# untitled.net
KiCad netlist of a schematic drawn in EAGLE
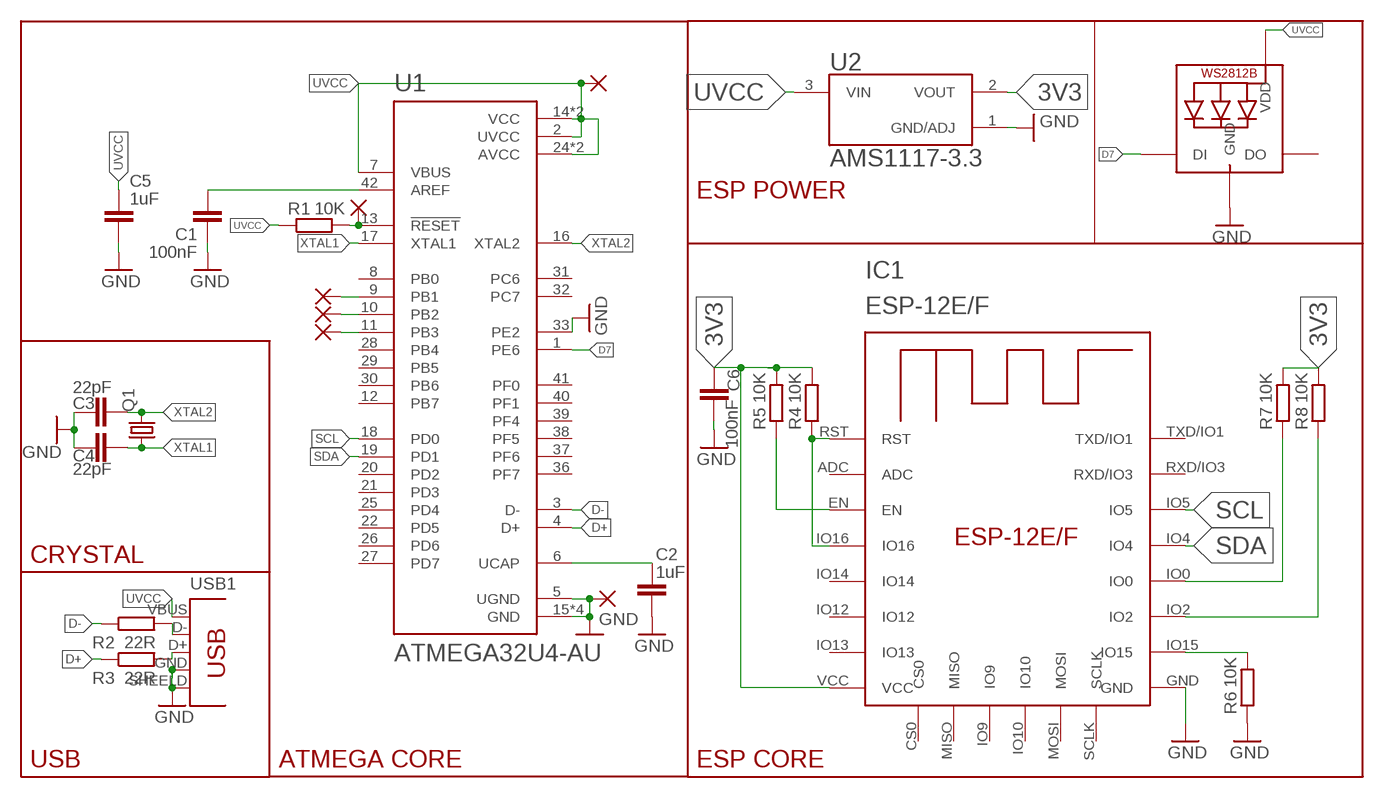
[diagram p0: schematic, sheet 1]

(export (version "E")
  (design (tool "Eeschema 10.0.6"))
  (components
    (comp (ref "C1")
      (value "100nF")
      (footprint "eagle-import:C0805")
      (libsource (lib "eagle-import") (part "C-EUC0805"))
    )
    (comp (ref "C2")
      (value "1uF")
      (footprint "eagle-import:C0805")
      (libsource (lib "eagle-import") (part "C-EUC0805"))
    )
    (comp (ref "C3")
      (value "22pF")
      (footprint "eagle-import:C0805")
      (libsource (lib "eagle-import") (part "C-EUC0805"))
    )
    (comp (ref "C4")
      (value "22pF")
      (footprint "eagle-import:C0805")
      (libsource (lib "eagle-import") (part "C-EUC0805"))
    )
    (comp (ref "C5")
      (value "1uF")
      (footprint "eagle-import:C0805")
      (libsource (lib "eagle-import") (part "C-EUC0805"))
    )
    (comp (ref "C6")
      (value "100nF")
      (footprint "eagle-import:C0805")
      (libsource (lib "eagle-import") (part "C-EUC0805"))
    )
    (comp (ref "IC1")
      (value "ESP-12E/F")
      (footprint "eagle-import:ESP-12E")
      (libsource (lib "eagle-import") (part "ESP-12E/F"))
    )
    (comp (ref "LED1")
      (value "WS2812B5050")
      (footprint "eagle-import:WS2812B")
      (fields (field (name "MF") "Worldsemi") (field (name "MP") "WS2812B"))
      (libsource (lib "eagle-import") (part "WS2812B5050"))
    )
    (comp (ref "PAD1")
      (value "1,6/0,8")
      (footprint "eagle-import:1,6_0,8")
      (libsource (lib "eagle-import") (part "1,6/0,8"))
    )
    (comp (ref "PAD2")
      (value "1,6/0,8")
      (footprint "eagle-import:1,6_0,8")
      (libsource (lib "eagle-import") (part "1,6/0,8"))
    )
    (comp (ref "PAD3")
      (value "1,6/0,8")
      (footprint "eagle-import:1,6_0,8")
      (libsource (lib "eagle-import") (part "1,6/0,8"))
    )
    (comp (ref "PAD4")
      (value "1,6/0,8")
      (footprint "eagle-import:1,6_0,8")
      (libsource (lib "eagle-import") (part "1,6/0,8"))
    )
    (comp (ref "PAD5")
      (value "1,6/0,8")
      (footprint "eagle-import:1,6_0,8")
      (libsource (lib "eagle-import") (part "1,6/0,8"))
    )
    (comp (ref "PAD6")
      (value "1,6/0,8")
      (footprint "eagle-import:1,6_0,8")
      (libsource (lib "eagle-import") (part "1,6/0,8"))
    )
    (comp (ref "Q1")
      (value "CRYSTALCTS406")
      (footprint "eagle-import:CTS406")
      (libsource (lib "eagle-import") (part "CRYSTALCTS406"))
    )
    (comp (ref "R1")
      (value "10K")
      (footprint "eagle-import:R0805")
      (libsource (lib "eagle-import") (part "R-EU_R0805"))
    )
    (comp (ref "R2")
      (value "22R")
      (footprint "eagle-import:R0805")
      (libsource (lib "eagle-import") (part "R-EU_R0805"))
    )
    (comp (ref "R3")
      (value "22R")
      (footprint "eagle-import:R0805")
      (libsource (lib "eagle-import") (part "R-EU_R0805"))
    )
    (comp (ref "R4")
      (value "10K")
      (footprint "eagle-import:R0805")
      (libsource (lib "eagle-import") (part "R-EU_R0805"))
    )
    (comp (ref "R5")
      (value "10K")
      (footprint "eagle-import:R0805")
      (libsource (lib "eagle-import") (part "R-EU_R0805"))
    )
    (comp (ref "R6")
      (value "10K")
      (footprint "eagle-import:R0805")
      (libsource (lib "eagle-import") (part "R-EU_R0805"))
    )
    (comp (ref "R7")
      (value "10K")
      (footprint "eagle-import:R0805")
      (libsource (lib "eagle-import") (part "R-EU_R0805"))
    )
    (comp (ref "R8")
      (value "10K")
      (footprint "eagle-import:R0805")
      (libsource (lib "eagle-import") (part "R-EU_R0805"))
    )
    (comp (ref "U1")
      (value "ATMEGA32U4-AU")
      (footprint "eagle-import:QFP80P1200X1200X120-44N")
      (fields (field (name "MF") "Microchip"))
      (libsource (lib "eagle-import") (part "ATMEGA32U4-AU"))
    )
    (comp (ref "U2")
      (value "AMS1117-3.3")
      (footprint "eagle-import:SOT229P700X180-4N")
      (fields (field (name "MF") "Advanced Monolithic Systems"))
      (libsource (lib "eagle-import") (part "AMS1117-3.3"))
    )
    (comp (ref "USB1")
      (value "TYPE-A-MALE-SHILED")
      (footprint "eagle-import:TYPE-A-MALE")
      (libsource (lib "eagle-import") (part "TYPE-A-MALE-SHILED"))
    )
  )
  (nets
    (net (code "1") (name "3V3") (class "Default")
      (node (ref "C6") (pin "1") (pinfunction "1_1") (pintype "passive"))
      (node (ref "IC1") (pin "VCC") (pinfunction "VCC_VCC") (pintype "power_in"))
      (node (ref "R4") (pin "2") (pinfunction "2_2") (pintype "passive"))
      (node (ref "R5") (pin "2") (pinfunction "2_2") (pintype "passive"))
      (node (ref "R7") (pin "2") (pinfunction "2_2") (pintype "passive"))
      (node (ref "R8") (pin "2") (pinfunction "2_2") (pintype "passive"))
      (node (ref "U2") (pin "2") (pinfunction "VOUT_2") (pintype "output"))
    )
    (net (code "2") (name "D+") (class "Default")
      (node (ref "R3") (pin "1") (pinfunction "1_1") (pintype "passive"))
      (node (ref "U1") (pin "4") (pinfunction "D+_4") (pintype "bidirectional"))
    )
    (net (code "3") (name "D-") (class "Default")
      (node (ref "R2") (pin "1") (pinfunction "1_1") (pintype "passive"))
      (node (ref "U1") (pin "3") (pinfunction "D-_3") (pintype "bidirectional"))
    )
    (net (code "4") (name "D7") (class "Default")
      (node (ref "LED1") (pin "4-DIN") (pinfunction "DI_4-DIN") (pintype "input"))
      (node (ref "U1") (pin "1") (pinfunction "PE6_1") (pintype "bidirectional"))
    )
    (net (code "5") (name "GND") (class "Default")
      (node (ref "C1") (pin "1") (pinfunction "1_1") (pintype "passive"))
      (node (ref "C2") (pin "2") (pinfunction "2_2") (pintype "passive"))
      (node (ref "C3") (pin "1") (pinfunction "1_1") (pintype "passive"))
      (node (ref "C4") (pin "1") (pinfunction "1_1") (pintype "passive"))
      (node (ref "C5") (pin "2") (pinfunction "2_2") (pintype "passive"))
      (node (ref "C6") (pin "2") (pinfunction "2_2") (pintype "passive"))
      (node (ref "IC1") (pin "GND") (pinfunction "GND_GND") (pintype "power_in"))
      (node (ref "LED1") (pin "3-GND") (pinfunction "GND_3-GND") (pintype "power_in"))
      (node (ref "PAD6") (pin "1") (pinfunction "P_1") (pintype "passive"))
      (node (ref "R6") (pin "1") (pinfunction "1_1") (pintype "passive"))
      (node (ref "U1") (pin "15") (pinfunction "GND_15") (pintype "power_in"))
      (node (ref "U1") (pin "23") (pinfunction "GND_23") (pintype "power_in"))
      (node (ref "U1") (pin "33") (pinfunction "PE2_33") (pintype "bidirectional"))
      (node (ref "U1") (pin "35") (pinfunction "GND_35") (pintype "power_in"))
      (node (ref "U1") (pin "43") (pinfunction "GND_43") (pintype "power_in"))
      (node (ref "U1") (pin "5") (pinfunction "UGND_5") (pintype "power_in"))
      (node (ref "U2") (pin "1") (pinfunction "GND/ADJ_1") (pintype "power_in"))
      (node (ref "USB1") (pin "GND") (pinfunction "4_GND") (pintype "power_in"))
      (node (ref "USB1") (pin "SHEELD") (pinfunction "5_SHEELD") (pintype "passive"))
    )
    (net (code "6") (name "Net-(IC1-PadEN)") (class "Default")
      (node (ref "IC1") (pin "EN") (pinfunction "EN_EN") (pintype "bidirectional"))
      (node (ref "R5") (pin "1") (pinfunction "1_1") (pintype "passive"))
    )
    (net (code "7") (name "Net-(IC1-PadIO0)") (class "Default")
      (node (ref "IC1") (pin "IO0") (pinfunction "IO0_IO0") (pintype "bidirectional"))
      (node (ref "R7") (pin "1") (pinfunction "1_1") (pintype "passive"))
    )
    (net (code "8") (name "Net-(IC1-PadIO2)") (class "Default")
      (node (ref "IC1") (pin "IO2") (pinfunction "IO2_IO2") (pintype "bidirectional"))
      (node (ref "R8") (pin "1") (pinfunction "1_1") (pintype "passive"))
    )
    (net (code "9") (name "Net-(IC1-PadIO15)") (class "Default")
      (node (ref "IC1") (pin "IO15") (pinfunction "IO15_IO15") (pintype "bidirectional"))
      (node (ref "R6") (pin "2") (pinfunction "2_2") (pintype "passive"))
    )
    (net (code "10") (name "Net-(IC1-PadIO16)") (class "Default")
      (node (ref "IC1") (pin "IO16") (pinfunction "IO16_IO16") (pintype "bidirectional"))
      (node (ref "IC1") (pin "RST") (pinfunction "RST_RST") (pintype "input"))
      (node (ref "R4") (pin "1") (pinfunction "1_1") (pintype "passive"))
    )
    (net (code "11") (name "Net-(PAD1-P)") (class "Default")
      (node (ref "PAD1") (pin "1") (pinfunction "P_1") (pintype "passive"))
      (node (ref "U1") (pin "9") (pinfunction "PB1_9") (pintype "bidirectional"))
    )
    (net (code "12") (name "Net-(PAD2-P)") (class "Default")
      (node (ref "PAD2") (pin "1") (pinfunction "P_1") (pintype "passive"))
      (node (ref "U1") (pin "10") (pinfunction "PB2_10") (pintype "bidirectional"))
    )
    (net (code "13") (name "Net-(PAD3-P)") (class "Default")
      (node (ref "PAD3") (pin "1") (pinfunction "P_1") (pintype "passive"))
      (node (ref "U1") (pin "11") (pinfunction "PB3_11") (pintype "bidirectional"))
    )
    (net (code "14") (name "Net-(PAD4-P)") (class "Default")
      (node (ref "PAD4") (pin "1") (pinfunction "P_1") (pintype "passive"))
      (node (ref "R1") (pin "2") (pinfunction "2_2") (pintype "passive"))
      (node (ref "U1") (pin "13") (pinfunction "~{RESET}_13") (pintype "input"))
    )
    (net (code "15") (name "Net-(U1-AREF)") (class "Default")
      (node (ref "C1") (pin "2") (pinfunction "2_2") (pintype "passive"))
      (node (ref "U1") (pin "42") (pinfunction "AREF_42") (pintype "input"))
    )
    (net (code "16") (name "Net-(U1-UCAP)") (class "Default")
      (node (ref "C2") (pin "1") (pinfunction "1_1") (pintype "passive"))
      (node (ref "U1") (pin "6") (pinfunction "UCAP_6") (pintype "passive"))
    )
    (net (code "17") (name "Net-(USB1-2)") (class "Default")
      (node (ref "R2") (pin "2") (pinfunction "2_2") (pintype "passive"))
      (node (ref "USB1") (pin "D-") (pinfunction "2_D-") (pintype "passive"))
    )
    (net (code "18") (name "Net-(USB1-3)") (class "Default")
      (node (ref "R3") (pin "2") (pinfunction "2_2") (pintype "passive"))
      (node (ref "USB1") (pin "D+") (pinfunction "3_D+") (pintype "passive"))
    )
    (net (code "19") (name "SCL") (class "Default")
      (node (ref "IC1") (pin "IO5") (pinfunction "IO5_IO5") (pintype "bidirectional"))
      (node (ref "U1") (pin "18") (pinfunction "PD0_18") (pintype "bidirectional"))
    )
    (net (code "20") (name "SDA") (class "Default")
      (node (ref "IC1") (pin "IO4") (pinfunction "IO4_IO4") (pintype "bidirectional"))
      (node (ref "U1") (pin "19") (pinfunction "PD1_19") (pintype "bidirectional"))
    )
    (net (code "21") (name "UVCC") (class "Default")
      (node (ref "C5") (pin "1") (pinfunction "1_1") (pintype "passive"))
      (node (ref "LED1") (pin "1-VDD") (pinfunction "VDD_1-VDD") (pintype "power_in"))
      (node (ref "PAD5") (pin "1") (pinfunction "P_1") (pintype "passive"))
      (node (ref "R1") (pin "1") (pinfunction "1_1") (pintype "passive"))
      (node (ref "U1") (pin "14") (pinfunction "VCC_14") (pintype "power_in"))
      (node (ref "U1") (pin "2") (pinfunction "UVCC_2") (pintype "power_in"))
      (node (ref "U1") (pin "24") (pinfunction "AVCC_24") (pintype "power_in"))
      (node (ref "U1") (pin "34") (pinfunction "VCC_34") (pintype "power_in"))
      (node (ref "U1") (pin "44") (pinfunction "AVCC_44") (pintype "power_in"))
      (node (ref "U1") (pin "7") (pinfunction "VBUS_7") (pintype "input"))
      (node (ref "U2") (pin "3") (pinfunction "VIN_3") (pintype "input"))
      (node (ref "USB1") (pin "VBUS") (pinfunction "1_VBUS") (pintype "power_in"))
    )
    (net (code "22") (name "XTAL1") (class "Default")
      (node (ref "C4") (pin "2") (pinfunction "2_2") (pintype "passive"))
      (node (ref "Q1") (pin "1") (pinfunction "1_1") (pintype "passive"))
      (node (ref "U1") (pin "17") (pinfunction "XTAL1_17") (pintype "input"))
    )
    (net (code "23") (name "XTAL2") (class "Default")
      (node (ref "C3") (pin "2") (pinfunction "2_2") (pintype "passive"))
      (node (ref "Q1") (pin "3") (pinfunction "2_3") (pintype "passive"))
      (node (ref "U1") (pin "16") (pinfunction "XTAL2_16") (pintype "output"))
    )
    (net (code "24") (name "unconnected-(IC1-PadADC)") (class "Default")
      (node (ref "IC1") (pin "ADC") (pinfunction "ADC_ADC") (pintype "bidirectional"))
    )
    (net (code "25") (name "unconnected-(IC1-PadCS0)") (class "Default")
      (node (ref "IC1") (pin "CS0") (pinfunction "CS0_CS0") (pintype "bidirectional"))
    )
    (net (code "26") (name "unconnected-(IC1-PadIO9)") (class "Default")
      (node (ref "IC1") (pin "IO9") (pinfunction "IO9_IO9") (pintype "bidirectional"))
    )
    (net (code "27") (name "unconnected-(IC1-PadIO10)") (class "Default")
      (node (ref "IC1") (pin "IO10") (pinfunction "IO10_IO10") (pintype "bidirectional"))
    )
    (net (code "28") (name "unconnected-(IC1-PadIO12)") (class "Default")
      (node (ref "IC1") (pin "IO12") (pinfunction "IO12_IO12") (pintype "bidirectional"))
    )
    (net (code "29") (name "unconnected-(IC1-PadIO13)") (class "Default")
      (node (ref "IC1") (pin "IO13") (pinfunction "IO13_IO13") (pintype "bidirectional"))
    )
    (net (code "30") (name "unconnected-(IC1-PadIO14)") (class "Default")
      (node (ref "IC1") (pin "IO14") (pinfunction "IO14_IO14") (pintype "bidirectional"))
    )
    (net (code "31") (name "unconnected-(IC1-PadMISO)") (class "Default")
      (node (ref "IC1") (pin "MISO") (pinfunction "MISO_MISO") (pintype "bidirectional"))
    )
    (net (code "32") (name "unconnected-(IC1-PadMOSI)") (class "Default")
      (node (ref "IC1") (pin "MOSI") (pinfunction "MOSI_MOSI") (pintype "bidirectional"))
    )
    (net (code "33") (name "unconnected-(IC1-PadRXD{slash}IO3)") (class "Default")
      (node (ref "IC1") (pin "RXD/IO3") (pinfunction "RXD/IO3_RXD/IO3") (pintype "bidirectional"))
    )
    (net (code "34") (name "unconnected-(IC1-PadSCLK)") (class "Default")
      (node (ref "IC1") (pin "SCLK") (pinfunction "SCLK_SCLK") (pintype "bidirectional"))
    )
    (net (code "35") (name "unconnected-(IC1-PadTXD{slash}IO1)") (class "Default")
      (node (ref "IC1") (pin "TXD/IO1") (pinfunction "TXD/IO1_TXD/IO1") (pintype "bidirectional"))
    )
    (net (code "36") (name "unconnected-(LED1-DO-Pad2-DOUT)") (class "Default")
      (node (ref "LED1") (pin "2-DOUT") (pinfunction "DO_2-DOUT") (pintype "output"))
    )
    (net (code "37") (name "unconnected-(U1-PB0-Pad8)") (class "Default")
      (node (ref "U1") (pin "8") (pinfunction "PB0_8") (pintype "bidirectional"))
    )
    (net (code "38") (name "unconnected-(U1-PB4-Pad28)") (class "Default")
      (node (ref "U1") (pin "28") (pinfunction "PB4_28") (pintype "bidirectional"))
    )
    (net (code "39") (name "unconnected-(U1-PB5-Pad29)") (class "Default")
      (node (ref "U1") (pin "29") (pinfunction "PB5_29") (pintype "bidirectional"))
    )
    (net (code "40") (name "unconnected-(U1-PB6-Pad30)") (class "Default")
      (node (ref "U1") (pin "30") (pinfunction "PB6_30") (pintype "bidirectional"))
    )
    (net (code "41") (name "unconnected-(U1-PB7-Pad12)") (class "Default")
      (node (ref "U1") (pin "12") (pinfunction "PB7_12") (pintype "bidirectional"))
    )
    (net (code "42") (name "unconnected-(U1-PC6-Pad31)") (class "Default")
      (node (ref "U1") (pin "31") (pinfunction "PC6_31") (pintype "bidirectional"))
    )
    (net (code "43") (name "unconnected-(U1-PC7-Pad32)") (class "Default")
      (node (ref "U1") (pin "32") (pinfunction "PC7_32") (pintype "bidirectional"))
    )
    (net (code "44") (name "unconnected-(U1-PD2-Pad20)") (class "Default")
      (node (ref "U1") (pin "20") (pinfunction "PD2_20") (pintype "bidirectional"))
    )
    (net (code "45") (name "unconnected-(U1-PD3-Pad21)") (class "Default")
      (node (ref "U1") (pin "21") (pinfunction "PD3_21") (pintype "bidirectional"))
    )
    (net (code "46") (name "unconnected-(U1-PD4-Pad25)") (class "Default")
      (node (ref "U1") (pin "25") (pinfunction "PD4_25") (pintype "bidirectional"))
    )
    (net (code "47") (name "unconnected-(U1-PD5-Pad22)") (class "Default")
      (node (ref "U1") (pin "22") (pinfunction "PD5_22") (pintype "bidirectional"))
    )
    (net (code "48") (name "unconnected-(U1-PD6-Pad26)") (class "Default")
      (node (ref "U1") (pin "26") (pinfunction "PD6_26") (pintype "bidirectional"))
    )
    (net (code "49") (name "unconnected-(U1-PD7-Pad27)") (class "Default")
      (node (ref "U1") (pin "27") (pinfunction "PD7_27") (pintype "bidirectional"))
    )
    (net (code "50") (name "unconnected-(U1-PF0-Pad41)") (class "Default")
      (node (ref "U1") (pin "41") (pinfunction "PF0_41") (pintype "bidirectional"))
    )
    (net (code "51") (name "unconnected-(U1-PF1-Pad40)") (class "Default")
      (node (ref "U1") (pin "40") (pinfunction "PF1_40") (pintype "bidirectional"))
    )
    (net (code "52") (name "unconnected-(U1-PF4-Pad39)") (class "Default")
      (node (ref "U1") (pin "39") (pinfunction "PF4_39") (pintype "bidirectional"))
    )
    (net (code "53") (name "unconnected-(U1-PF5-Pad38)") (class "Default")
      (node (ref "U1") (pin "38") (pinfunction "PF5_38") (pintype "bidirectional"))
    )
    (net (code "54") (name "unconnected-(U1-PF6-Pad37)") (class "Default")
      (node (ref "U1") (pin "37") (pinfunction "PF6_37") (pintype "bidirectional"))
    )
    (net (code "55") (name "unconnected-(U1-PF7-Pad36)") (class "Default")
      (node (ref "U1") (pin "36") (pinfunction "PF7_36") (pintype "bidirectional"))
    )
  )
)
